# wxeda-sd-mod.net
KiCad netlist of a schematic drawn in EAGLE
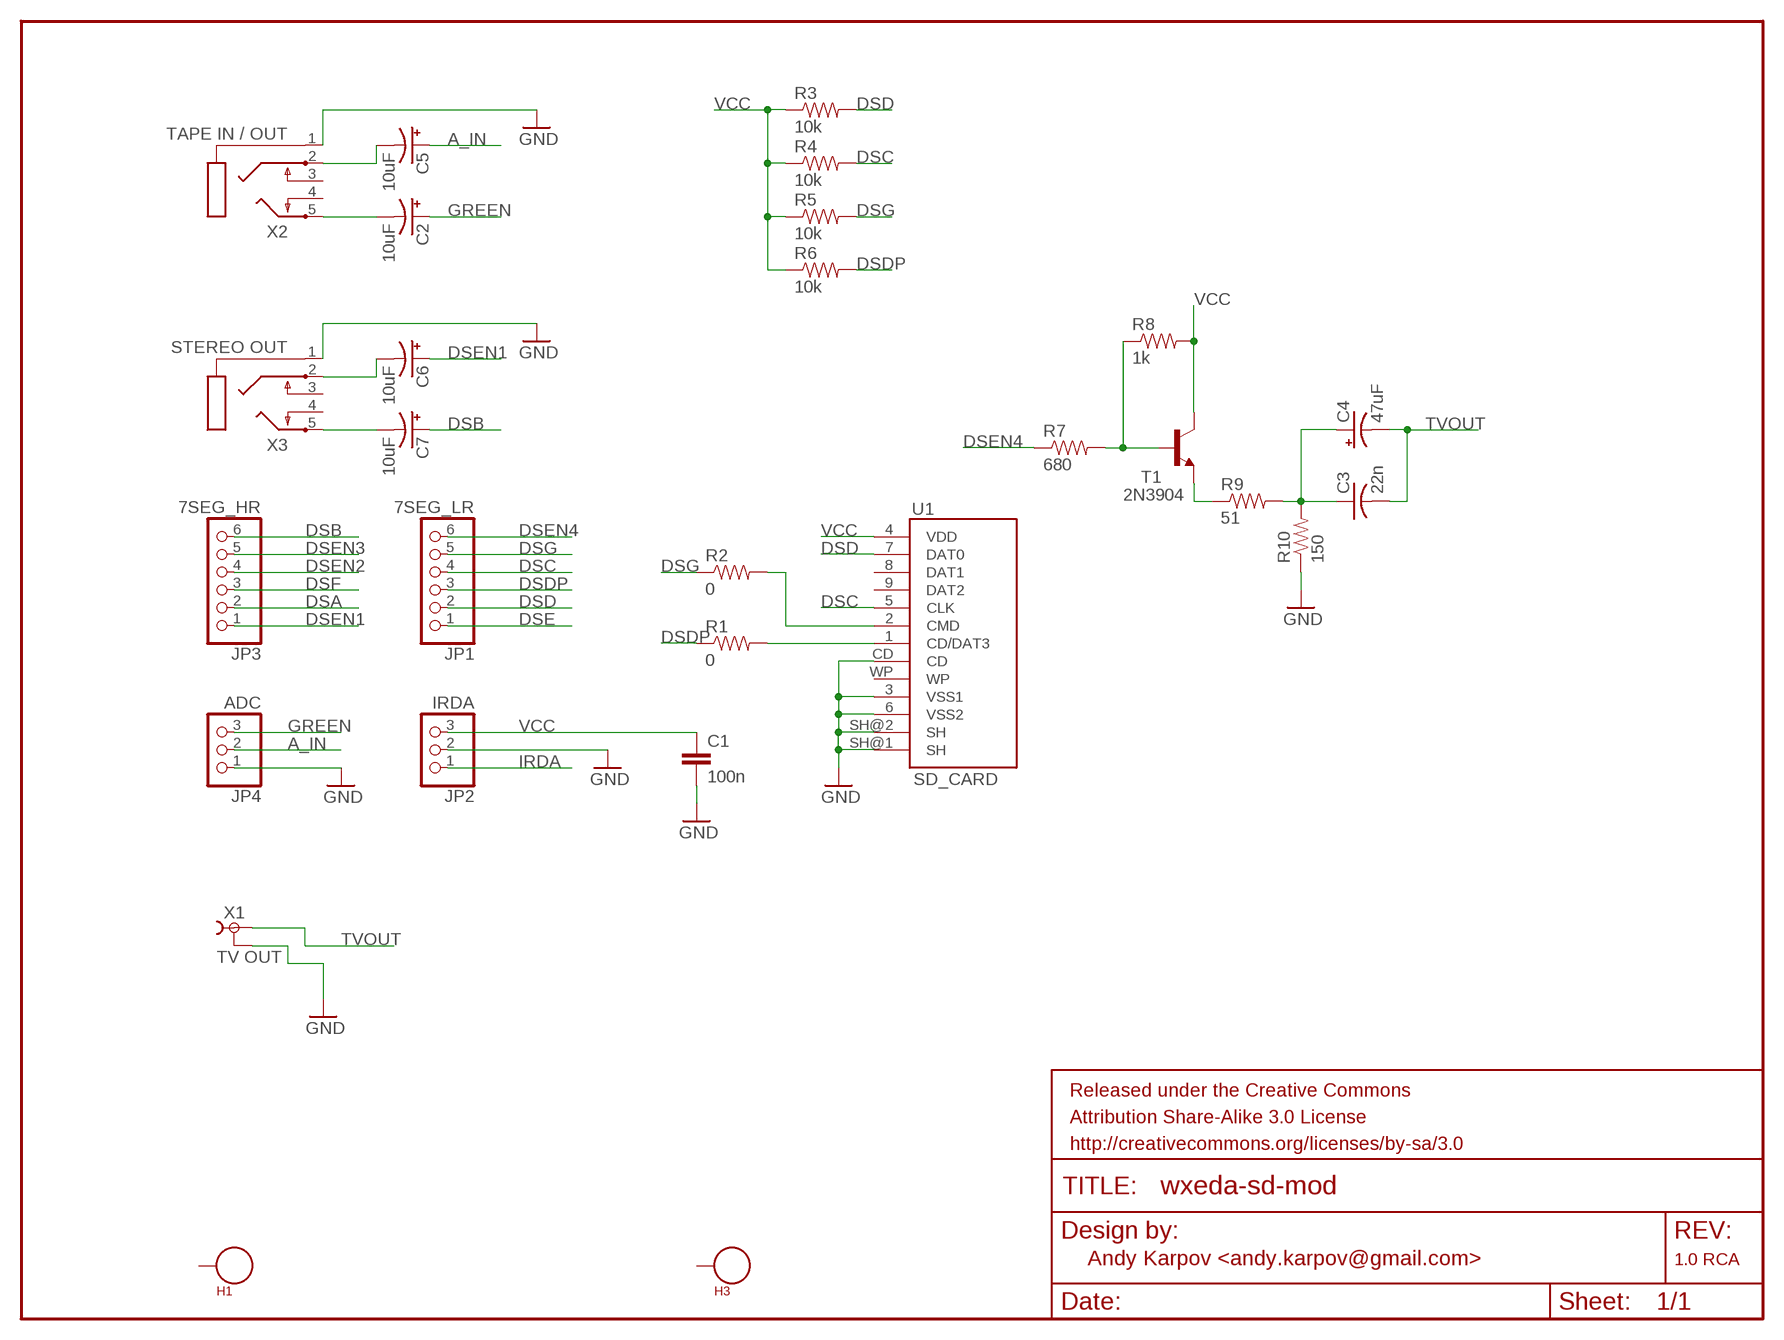
[diagram p0: schematic, sheet 1]

(export (version "E")
  (design (tool "Eeschema 10.0.6"))
  (components
    (comp (ref "C1")
      (value "100n")
      (footprint "eagle-import:1206")
      (libsource (lib "eagle-import") (part "CAP1206"))
    )
    (comp (ref "C2")
      (value "10uF")
      (footprint "eagle-import:E2,5-6E")
      (libsource (lib "eagle-import") (part "CPOL-USE2,5-6E"))
    )
    (comp (ref "C3")
      (value "22n")
      (footprint "eagle-import:C050-025X075")
      (libsource (lib "eagle-import") (part "C-US050-025X075"))
    )
    (comp (ref "C4")
      (value "47uF")
      (footprint "eagle-import:E2,5-6E")
      (libsource (lib "eagle-import") (part "CPOL-USE2,5-6E"))
    )
    (comp (ref "C5")
      (value "10uF")
      (footprint "eagle-import:E2,5-6E")
      (libsource (lib "eagle-import") (part "CPOL-USE2,5-6E"))
    )
    (comp (ref "C6")
      (value "10uF")
      (footprint "eagle-import:E2,5-6E")
      (libsource (lib "eagle-import") (part "CPOL-USE2,5-6E"))
    )
    (comp (ref "C7")
      (value "10uF")
      (footprint "eagle-import:E2,5-6E")
      (libsource (lib "eagle-import") (part "CPOL-USE2,5-6E"))
    )
    (comp (ref "FRAME1")
      (value "FRAME-LETTER")
      (footprint "eagle-import:CREATIVE_COMMONS")
      (libsource (lib "eagle-import") (part "FRAME-LETTER"))
    )
    (comp (ref "H1")
      (value "SEW_HOLE")
      (footprint "eagle-import:SIMPLE_HOLE")
      (libsource (lib "eagle-import") (part "SEW_HOLE"))
    )
    (comp (ref "H3")
      (value "SEW_HOLE")
      (footprint "eagle-import:SIMPLE_HOLE")
      (libsource (lib "eagle-import") (part "SEW_HOLE"))
    )
    (comp (ref "JP1")
      (value "7SEG_LR")
      (footprint "eagle-import:1X06")
      (libsource (lib "eagle-import") (part "PINHD-1X6"))
    )
    (comp (ref "JP2")
      (value "IRDA")
      (footprint "eagle-import:1X03")
      (libsource (lib "eagle-import") (part "PINHD-1X3"))
    )
    (comp (ref "JP3")
      (value "7SEG_HR")
      (footprint "eagle-import:1X06")
      (libsource (lib "eagle-import") (part "PINHD-1X6"))
    )
    (comp (ref "JP4")
      (value "ADC")
      (footprint "eagle-import:1X03")
      (libsource (lib "eagle-import") (part "PINHD-1X3"))
    )
    (comp (ref "R1")
      (value "0")
      (footprint "eagle-import:AXIAL-0.3")
      (libsource (lib "eagle-import") (part "RESISTORAXIAL-0.3"))
    )
    (comp (ref "R2")
      (value "0")
      (footprint "eagle-import:AXIAL-0.3")
      (libsource (lib "eagle-import") (part "RESISTORAXIAL-0.3"))
    )
    (comp (ref "R3")
      (value "10k")
      (footprint "eagle-import:AXIAL-0.3")
      (libsource (lib "eagle-import") (part "RESISTORAXIAL-0.3"))
    )
    (comp (ref "R4")
      (value "10k")
      (footprint "eagle-import:AXIAL-0.3")
      (libsource (lib "eagle-import") (part "RESISTORAXIAL-0.3"))
    )
    (comp (ref "R5")
      (value "10k")
      (footprint "eagle-import:AXIAL-0.3")
      (libsource (lib "eagle-import") (part "RESISTORAXIAL-0.3"))
    )
    (comp (ref "R6")
      (value "10k")
      (footprint "eagle-import:AXIAL-0.3")
      (libsource (lib "eagle-import") (part "RESISTORAXIAL-0.3"))
    )
    (comp (ref "R7")
      (value "680")
      (footprint "eagle-import:AXIAL-0.3")
      (libsource (lib "eagle-import") (part "RESISTORAXIAL-0.3"))
    )
    (comp (ref "R8")
      (value "1k")
      (footprint "eagle-import:AXIAL-0.3")
      (libsource (lib "eagle-import") (part "RESISTORAXIAL-0.3"))
    )
    (comp (ref "R9")
      (value "51")
      (footprint "eagle-import:AXIAL-0.3")
      (libsource (lib "eagle-import") (part "RESISTORAXIAL-0.3"))
    )
    (comp (ref "R10")
      (value "150")
      (footprint "eagle-import:AXIAL-0.3")
      (libsource (lib "eagle-import") (part "RESISTORAXIAL-0.3"))
    )
    (comp (ref "T1")
      (value "2N3904")
      (footprint "eagle-import:TO92")
      (libsource (lib "eagle-import") (part "2N3904"))
    )
    (comp (ref "U1")
      (value "SD_CARD")
      (footprint "eagle-import:SDCARD_4UCONN")
      (libsource (lib "eagle-import") (part "SD_CARD_SOCKET4UCON"))
    )
    (comp (ref "X1")
      (value "TV OUT")
      (footprint "eagle-import:TOBU3")
      (fields (field (name "MF") "FARNELL") (field (name "MPN") "TOBU 3"))
      (libsource (lib "eagle-import") (part "TOBU3"))
    )
    (comp (ref "X2")
      (value "TAPE IN / OUT")
      (footprint "eagle-import:STX3100")
      (libsource (lib "eagle-import") (part "STEREOJACK"))
    )
    (comp (ref "X3")
      (value "STEREO OUT")
      (footprint "eagle-import:STX3100")
      (libsource (lib "eagle-import") (part "STEREOJACK"))
    )
  )
  (nets
    (net (code "1") (name "/A_IN") (class "Default")
      (node (ref "C5") (pin "+") (pinfunction "+_+") (pintype "passive"))
      (node (ref "JP4") (pin "2") (pinfunction "2_2") (pintype "passive"))
    )
    (net (code "2") (name "/DSA") (class "Default")
      (node (ref "JP3") (pin "2") (pinfunction "2_2") (pintype "passive"))
    )
    (net (code "3") (name "/DSB") (class "Default")
      (node (ref "C7") (pin "+") (pinfunction "+_+") (pintype "passive"))
      (node (ref "JP3") (pin "6") (pinfunction "6_6") (pintype "passive"))
    )
    (net (code "4") (name "/DSC") (class "Default")
      (node (ref "JP1") (pin "4") (pinfunction "4_4") (pintype "passive"))
      (node (ref "R4") (pin "P$2") (pinfunction "2_P$2") (pintype "passive"))
      (node (ref "U1") (pin "5") (pinfunction "CLK_5") (pintype "bidirectional"))
    )
    (net (code "5") (name "/DSD") (class "Default")
      (node (ref "JP1") (pin "2") (pinfunction "2_2") (pintype "passive"))
      (node (ref "R3") (pin "P$2") (pinfunction "2_P$2") (pintype "passive"))
      (node (ref "U1") (pin "7") (pinfunction "DAT0_7") (pintype "bidirectional"))
    )
    (net (code "6") (name "/DSDP") (class "Default")
      (node (ref "JP1") (pin "3") (pinfunction "3_3") (pintype "passive"))
      (node (ref "R1") (pin "P$1") (pinfunction "1_P$1") (pintype "passive"))
      (node (ref "R6") (pin "P$2") (pinfunction "2_P$2") (pintype "passive"))
    )
    (net (code "7") (name "/DSE") (class "Default")
      (node (ref "JP1") (pin "1") (pinfunction "1_1") (pintype "passive"))
    )
    (net (code "8") (name "/DSEN1") (class "Default")
      (node (ref "C6") (pin "+") (pinfunction "+_+") (pintype "passive"))
      (node (ref "JP3") (pin "1") (pinfunction "1_1") (pintype "passive"))
    )
    (net (code "9") (name "/DSEN2") (class "Default")
      (node (ref "JP3") (pin "4") (pinfunction "4_4") (pintype "passive"))
    )
    (net (code "10") (name "/DSEN3") (class "Default")
      (node (ref "JP3") (pin "5") (pinfunction "5_5") (pintype "passive"))
    )
    (net (code "11") (name "/DSEN4") (class "Default")
      (node (ref "JP1") (pin "6") (pinfunction "6_6") (pintype "passive"))
      (node (ref "R7") (pin "P$1") (pinfunction "1_P$1") (pintype "passive"))
    )
    (net (code "12") (name "/DSF") (class "Default")
      (node (ref "JP3") (pin "3") (pinfunction "3_3") (pintype "passive"))
    )
    (net (code "13") (name "/DSG") (class "Default")
      (node (ref "JP1") (pin "5") (pinfunction "5_5") (pintype "passive"))
      (node (ref "R2") (pin "P$1") (pinfunction "1_P$1") (pintype "passive"))
      (node (ref "R5") (pin "P$2") (pinfunction "2_P$2") (pintype "passive"))
    )
    (net (code "14") (name "/GREEN") (class "Default")
      (node (ref "C2") (pin "+") (pinfunction "+_+") (pintype "passive"))
      (node (ref "JP4") (pin "3") (pinfunction "3_3") (pintype "passive"))
    )
    (net (code "15") (name "/IRDA") (class "Default")
      (node (ref "JP2") (pin "1") (pinfunction "1_1") (pintype "passive"))
    )
    (net (code "16") (name "/TVOUT") (class "Default")
      (node (ref "C3") (pin "2") (pinfunction "2_2") (pintype "passive"))
      (node (ref "C4") (pin "-") (pinfunction "-_-") (pintype "passive"))
      (node (ref "X1") (pin "1") (pinfunction "1_1") (pintype "passive"))
    )
    (net (code "17") (name "/VCC") (class "Default")
      (node (ref "C1") (pin "1") (pinfunction "1_1") (pintype "passive"))
      (node (ref "JP2") (pin "3") (pinfunction "3_3") (pintype "passive"))
      (node (ref "R3") (pin "P$1") (pinfunction "1_P$1") (pintype "passive"))
      (node (ref "R4") (pin "P$1") (pinfunction "1_P$1") (pintype "passive"))
      (node (ref "R5") (pin "P$1") (pinfunction "1_P$1") (pintype "passive"))
      (node (ref "R6") (pin "P$1") (pinfunction "1_P$1") (pintype "passive"))
      (node (ref "R8") (pin "P$2") (pinfunction "2_P$2") (pintype "passive"))
      (node (ref "T1") (pin "1") (pinfunction "C_1") (pintype "passive"))
      (node (ref "U1") (pin "4") (pinfunction "VDD_4") (pintype "power_in"))
    )
    (net (code "18") (name "GND") (class "Default")
      (node (ref "C1") (pin "2") (pinfunction "2_2") (pintype "passive"))
      (node (ref "JP2") (pin "2") (pinfunction "2_2") (pintype "passive"))
      (node (ref "JP4") (pin "1") (pinfunction "1_1") (pintype "passive"))
      (node (ref "R10") (pin "P$1") (pinfunction "1_P$1") (pintype "passive"))
      (node (ref "U1") (pin "3") (pinfunction "VSS1_3") (pintype "power_in"))
      (node (ref "U1") (pin "6") (pinfunction "VSS2_6") (pintype "power_in"))
      (node (ref "U1") (pin "CD") (pinfunction "CD_CD") (pintype "bidirectional"))
      (node (ref "U1") (pin "SH@1") (pinfunction "SH_SH@1") (pintype "bidirectional"))
      (node (ref "U1") (pin "SH@2") (pinfunction "SH_SH@2") (pintype "bidirectional"))
      (node (ref "X1") (pin "2") (pinfunction "2_2") (pintype "passive"))
      (node (ref "X1") (pin "2@1") (pinfunction "2_2@1") (pintype "passive"))
      (node (ref "X1") (pin "2@2") (pinfunction "2_2@2") (pintype "passive"))
      (node (ref "X2") (pin "1") (pinfunction "1_1") (pintype "passive"))
      (node (ref "X3") (pin "1") (pinfunction "1_1") (pintype "passive"))
    )
    (net (code "19") (name "Net-(C2-Pad-)") (class "Default")
      (node (ref "C2") (pin "-") (pinfunction "-_-") (pintype "passive"))
      (node (ref "X2") (pin "5") (pinfunction "5_5") (pintype "passive"))
    )
    (net (code "20") (name "Net-(C5-Pad-)") (class "Default")
      (node (ref "C5") (pin "-") (pinfunction "-_-") (pintype "passive"))
      (node (ref "X2") (pin "2") (pinfunction "2_2") (pintype "passive"))
    )
    (net (code "21") (name "Net-(C6-Pad-)") (class "Default")
      (node (ref "C6") (pin "-") (pinfunction "-_-") (pintype "passive"))
      (node (ref "X3") (pin "2") (pinfunction "2_2") (pintype "passive"))
    )
    (net (code "22") (name "Net-(C7-Pad-)") (class "Default")
      (node (ref "C7") (pin "-") (pinfunction "-_-") (pintype "passive"))
      (node (ref "X3") (pin "5") (pinfunction "5_5") (pintype "passive"))
    )
    (net (code "23") (name "Net-(R1-2)") (class "Default")
      (node (ref "R1") (pin "P$2") (pinfunction "2_P$2") (pintype "passive"))
      (node (ref "U1") (pin "1") (pinfunction "CD/DAT3_1") (pintype "bidirectional"))
    )
    (net (code "24") (name "Net-(R2-2)") (class "Default")
      (node (ref "R2") (pin "P$2") (pinfunction "2_P$2") (pintype "passive"))
      (node (ref "U1") (pin "2") (pinfunction "CMD_2") (pintype "bidirectional"))
    )
    (net (code "25") (name "Net-(R7-2)") (class "Default")
      (node (ref "R7") (pin "P$2") (pinfunction "2_P$2") (pintype "passive"))
      (node (ref "R8") (pin "P$1") (pinfunction "1_P$1") (pintype "passive"))
      (node (ref "T1") (pin "2") (pinfunction "B_2") (pintype "passive"))
    )
    (net (code "26") (name "Net-(R9-1)") (class "Default")
      (node (ref "R9") (pin "P$1") (pinfunction "1_P$1") (pintype "passive"))
      (node (ref "T1") (pin "3") (pinfunction "E_3") (pintype "passive"))
    )
    (net (code "27") (name "Net-(R10-2)") (class "Default")
      (node (ref "C3") (pin "1") (pinfunction "1_1") (pintype "passive"))
      (node (ref "C4") (pin "+") (pinfunction "+_+") (pintype "passive"))
      (node (ref "R10") (pin "P$2") (pinfunction "2_P$2") (pintype "passive"))
      (node (ref "R9") (pin "P$2") (pinfunction "2_P$2") (pintype "passive"))
    )
    (net (code "28") (name "unconnected-(H1-PadP$1)") (class "Default")
      (node (ref "H1") (pin "P$1") (pinfunction "P$1_P$1") (pintype "bidirectional"))
    )
    (net (code "29") (name "unconnected-(H3-PadP$1)") (class "Default")
      (node (ref "H3") (pin "P$1") (pinfunction "P$1_P$1") (pintype "bidirectional"))
    )
    (net (code "30") (name "unconnected-(U1-DAT1-Pad8)") (class "Default")
      (node (ref "U1") (pin "8") (pinfunction "DAT1_8") (pintype "bidirectional"))
    )
    (net (code "31") (name "unconnected-(U1-DAT2-Pad9)") (class "Default")
      (node (ref "U1") (pin "9") (pinfunction "DAT2_9") (pintype "bidirectional"))
    )
    (net (code "32") (name "unconnected-(U1-PadWP)") (class "Default")
      (node (ref "U1") (pin "WP") (pinfunction "WP_WP") (pintype "bidirectional"))
    )
    (net (code "33") (name "unconnected-(X2-Pad3)") (class "Default")
      (node (ref "X2") (pin "3") (pinfunction "3_3") (pintype "passive"))
    )
    (net (code "34") (name "unconnected-(X2-Pad4)") (class "Default")
      (node (ref "X2") (pin "4") (pinfunction "4_4") (pintype "passive"))
    )
    (net (code "35") (name "unconnected-(X3-Pad3)") (class "Default")
      (node (ref "X3") (pin "3") (pinfunction "3_3") (pintype "passive"))
    )
    (net (code "36") (name "unconnected-(X3-Pad4)") (class "Default")
      (node (ref "X3") (pin "4") (pinfunction "4_4") (pintype "passive"))
    )
  )
)
